# RADC-Power-S05-V00.net
KiCad netlist of a schematic drawn in Altium Designer
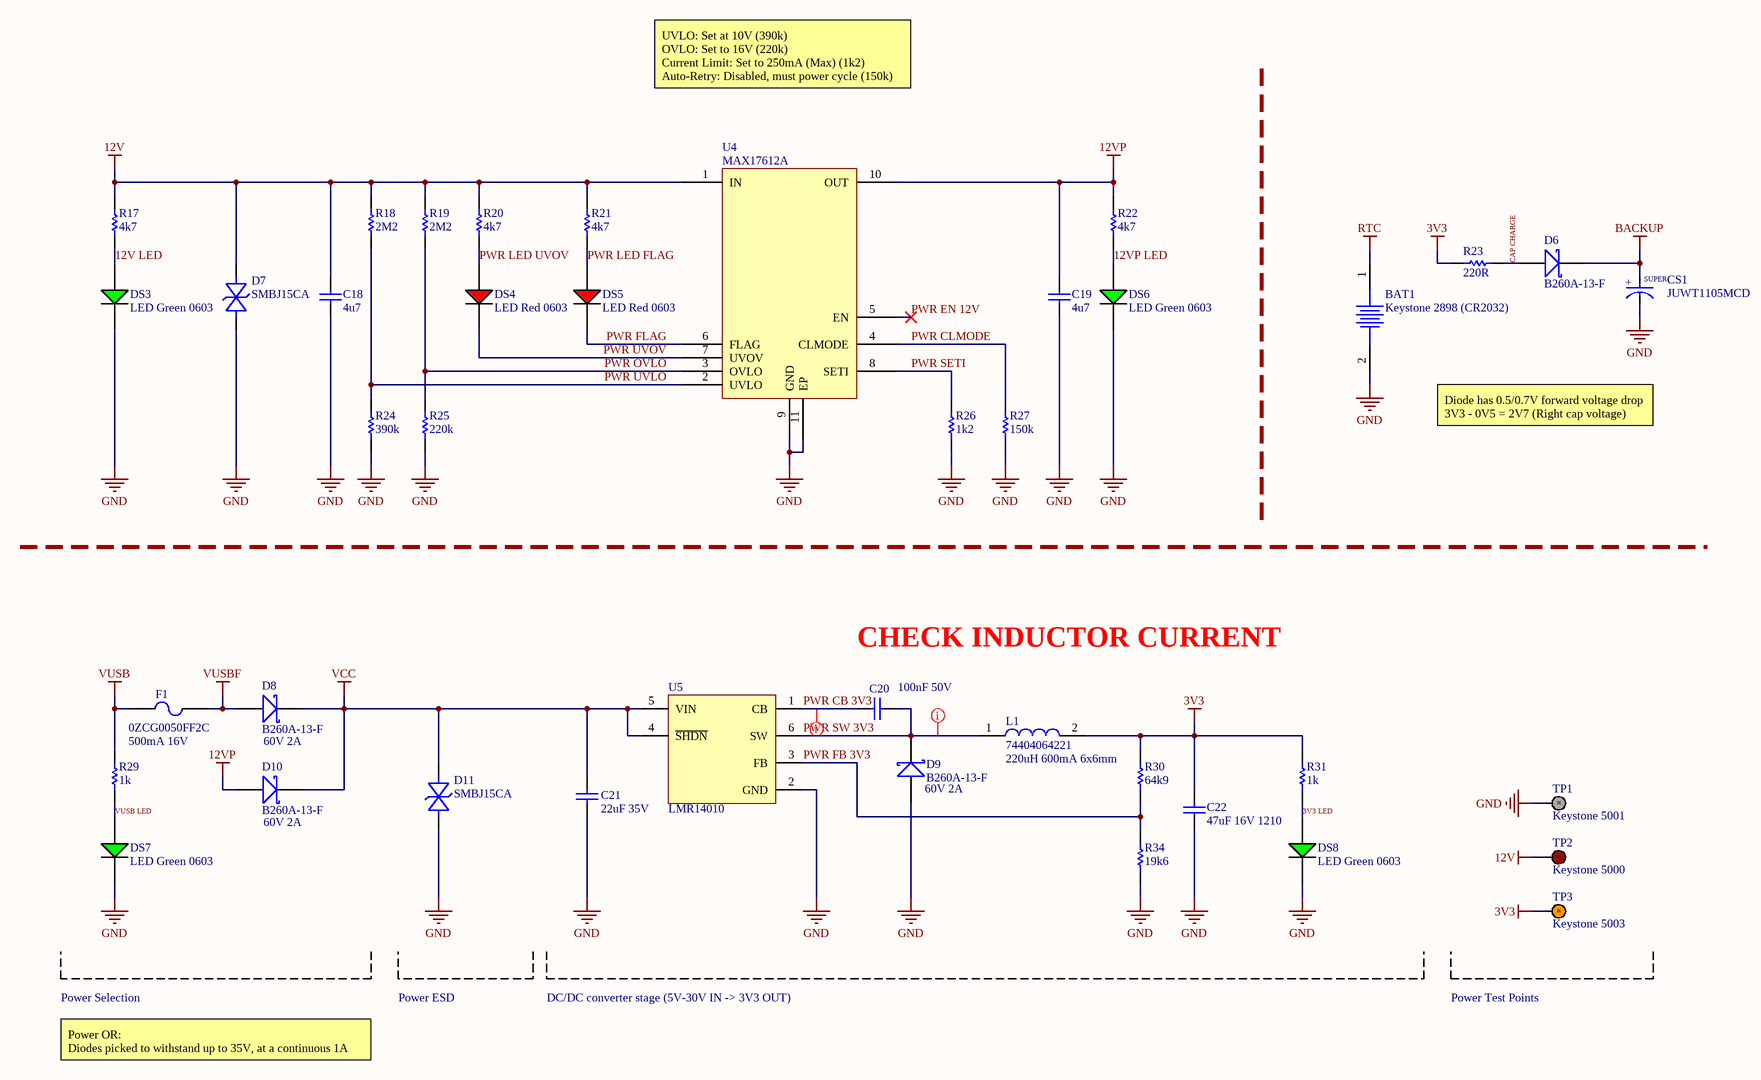
[diagram p0: RADC-Power-S05-V00.SchDoc]

(export (version "E")
  (design (tool "Eeschema 10.0.6"))
  (components
    (comp (ref "BAT1")
      (value "Keystone 2898 (CR2032)")
      (footprint "Keystone 2898")
      (description "Battery Retainer Coin, 20.0mm 1 Cell SMD (SMT) Tab")
      (libsource (lib "QUTMS_PowerSupplyLibrary") (part "Keystone 2898"))
    )
    (comp (ref "C18")
      (value "4u7")
      (footprint "Cap_Ceramic_0603")
      (description "Capacitor, Ceramic, SMD, 4u7, 50V, 5%, X7R, 0603")
      (libsource (lib "StandardCapacitors") (part "4u7 50V 5% X7R 0603"))
    )
    (comp (ref "C19")
      (value "4u7")
      (footprint "Cap_Ceramic_0603")
      (description "Capacitor, Ceramic, SMD, 4u7, 50V, 5%, X7R, 0603")
      (libsource (lib "StandardCapacitors") (part "4u7 50V 5% X7R 0603"))
    )
    (comp (ref "C20")
      (value "100nF 50V")
      (footprint "Cap_Ceramic_0603")
      (description "Capacitor, Ceramic, SMD, 100nF, 50V, 5%, X7R, 0603")
      (libsource (lib "StandardCapacitors") (part "100nF 50V 5% X7R 0603"))
    )
    (comp (ref "C21")
      (value "22uF 35V")
      (footprint "Cap_Ceramic_1206")
      (description "22µF ±20% 35V Ceramic Capacitor X5R 1206 (3216 Metric)")
      (libsource (lib "StandardCapacitors") (part "22uF 35V 20% X5R 1206"))
    )
    (comp (ref "C22")
      (value "47uF 16V 1210")
      (footprint "Cap_Ceramic_1210")
      (description "Capacitor, Ceramic, SMD, 47uF, 16V, 5%, X7R, 1210")
      (libsource (lib "StandardCapacitors") (part "47uF 16V 10% X7R 1210"))
    )
    (comp (ref "CS1")
      (value "JUWT1105MCD")
      (footprint "CAP_ALU_6.3mmD_9mmL")
      (description "1F (EDLC) Supercapacitor 2.7V Radial, Can 4Ohm @ 1kHz 1000 Hrs @ 70°C")
      (libsource (lib "StandardCapacitors") (part "JUWT1105MCD"))
    )
    (comp (ref "D6")
      (value "B260A-13-F")
      (footprint "SMA")
      (description "Diode, Schottky Barrier Rectifier, 60 V, 2 A, B260A-13-F")
      (libsource (lib "QUTMS_DiodeLibrary") (part "B260A-13-F"))
    )
    (comp (ref "D7")
      (value "SMBJ15CA")
      (footprint "SMB")
      (description "Diode, SMD, TVS Diode, 15V 24.4V, DO214AA/SMB")
      (libsource (lib "QUTMS_DiodeLibrary") (part "SMBJ15CA"))
    )
    (comp (ref "D8")
      (value "B260A-13-F")
      (footprint "SMA")
      (description "Diode, Schottky Barrier Rectifier, 60 V, 2 A, B260A-13-F")
      (libsource (lib "QUTMS_DiodeLibrary") (part "B260A-13-F"))
    )
    (comp (ref "D9")
      (value "B260A-13-F")
      (footprint "SMA")
      (description "Diode, Schottky Barrier Rectifier, 60 V, 2 A, B260A-13-F")
      (libsource (lib "QUTMS_DiodeLibrary") (part "B260A-13-F"))
    )
    (comp (ref "D10")
      (value "B260A-13-F")
      (footprint "SMA")
      (description "Diode, Schottky Barrier Rectifier, 60 V, 2 A, B260A-13-F")
      (libsource (lib "QUTMS_DiodeLibrary") (part "B260A-13-F"))
    )
    (comp (ref "D11")
      (value "SMBJ15CA")
      (footprint "SMB")
      (description "Diode, SMD, TVS Diode, 15V 24.4V, DO214AA/SMB")
      (libsource (lib "QUTMS_DiodeLibrary") (part "SMBJ15CA"))
    )
    (comp (ref "DS3")
      (value "LED Green 0603")
      (footprint "LED GREEN 0603")
      (libsource (lib "QUTMS_LEDLibrary") (part "LED Green 0603"))
    )
    (comp (ref "DS4")
      (value "LED Red 0603")
      (footprint "LED RED 0603")
      (libsource (lib "QUTMS_LEDLibrary") (part "LED Red 0603"))
    )
    (comp (ref "DS5")
      (value "LED Red 0603")
      (footprint "LED RED 0603")
      (libsource (lib "QUTMS_LEDLibrary") (part "LED Red 0603"))
    )
    (comp (ref "DS6")
      (value "LED Green 0603")
      (footprint "LED GREEN 0603")
      (libsource (lib "QUTMS_LEDLibrary") (part "LED Green 0603"))
    )
    (comp (ref "DS7")
      (value "LED Green 0603")
      (footprint "LED GREEN 0603")
      (libsource (lib "QUTMS_LEDLibrary") (part "LED Green 0603"))
    )
    (comp (ref "DS8")
      (value "LED Green 0603")
      (footprint "LED GREEN 0603")
      (libsource (lib "QUTMS_LEDLibrary") (part "LED Green 0603"))
    )
    (comp (ref "F1")
      (value "0ZCG0050FF2C")
      (footprint "1812 FUSE")
      (description "Polymeric PTC Resettable Fuse 16V 500mA Ih Surface Mount 1812 (4532 Metric), Concave")
      (libsource (lib "QUTMS_FuseLibrary") (part "0ZCG0050FF2C"))
    )
    (comp (ref "L1")
      (value "74404064221")
      (footprint "Inductor_6x6mm")
      (description "FIXED IND 220UH 660MA 850 MOHM")
      (libsource (lib "QUTMS_InductorLibrary") (part "74404064221"))
    )
    (comp (ref "R17")
      (value "4k7")
      (footprint "Res_ThinFilm_0603")
      (description "Resistor, SMD, 4k7, 0.1W, 5%, 0603")
      (libsource (lib "StandardResistors") (part "4k7 5% 0603"))
    )
    (comp (ref "R18")
      (value "2M2")
      (footprint "Res_ThinFilm_0603")
      (description "Resistor, SMD, 2M2, 0.1W, 5%, 0603")
      (libsource (lib "StandardResistors") (part "2M2 5% 0603"))
    )
    (comp (ref "R19")
      (value "2M2")
      (footprint "Res_ThinFilm_0603")
      (description "Resistor, SMD, 2M2, 0.1W, 5%, 0603")
      (libsource (lib "StandardResistors") (part "2M2 5% 0603"))
    )
    (comp (ref "R20")
      (value "4k7")
      (footprint "Res_ThinFilm_0603")
      (description "Resistor, SMD, 4k7, 0.1W, 5%, 0603")
      (libsource (lib "StandardResistors") (part "4k7 5% 0603"))
    )
    (comp (ref "R21")
      (value "4k7")
      (footprint "Res_ThinFilm_0603")
      (description "Resistor, SMD, 4k7, 0.1W, 5%, 0603")
      (libsource (lib "StandardResistors") (part "4k7 5% 0603"))
    )
    (comp (ref "R22")
      (value "4k7")
      (footprint "Res_ThinFilm_0603")
      (description "Resistor, SMD, 4k7, 0.1W, 5%, 0603")
      (libsource (lib "StandardResistors") (part "4k7 5% 0603"))
    )
    (comp (ref "R23")
      (value "220R")
      (footprint "Res_ThinFilm_0603")
      (description "Resistor, SMD, 220R, 0.1W, 5%, 0603")
      (libsource (lib "StandardResistors") (part "220R 5% 0603"))
    )
    (comp (ref "R24")
      (value "390k")
      (footprint "Res_ThinFilm_0603")
      (description "Resistor, SMD, 390k, 0.1W, 5%, 0603")
      (libsource (lib "StandardResistors") (part "390k 5% 0603"))
    )
    (comp (ref "R25")
      (value "220k")
      (footprint "Res_ThinFilm_0603")
      (description "Resistor, SMD, 220k, 0.1W, 5%, 0603")
      (libsource (lib "StandardResistors") (part "220k 5% 0603"))
    )
    (comp (ref "R26")
      (value "1k2")
      (footprint "Res_ThinFilm_0603")
      (description "Resistor, SMD, 1k2, 0.1W, 5%, 0603")
      (libsource (lib "StandardResistors") (part "1k2 5% 0603"))
    )
    (comp (ref "R27")
      (value "150k")
      (footprint "Res_ThinFilm_0603")
      (description "Resistor, SMD, 150k, 0.1W, 5%, 0603")
      (libsource (lib "StandardResistors") (part "150k 5%, 0603"))
    )
    (comp (ref "R29")
      (value "1k")
      (footprint "Res_ThinFilm_0603")
      (description "Resistor, SMD, 1k, 0.1W, 5%, 0603")
      (libsource (lib "StandardResistors") (part "1k 5% 0603"))
    )
    (comp (ref "R30")
      (value "64k9")
      (footprint "Res_ThinFilm_0603")
      (description "Resistor, SMD, 64k9, 0.1W, 5%, 0603")
      (libsource (lib "StandardResistors") (part "64k9 1% 0603"))
    )
    (comp (ref "R31")
      (value "1k")
      (footprint "Res_ThinFilm_0603")
      (description "Resistor, SMD, 1k, 0.1W, 5%, 0603")
      (libsource (lib "StandardResistors") (part "1k 5% 0603"))
    )
    (comp (ref "R34")
      (value "19k6")
      (footprint "Res_ThinFilm_0603")
      (description "Resistor, SMD, 19k6, 0.1W, 5%, 0603")
      (libsource (lib "StandardResistors") (part "19k6 1% 0603"))
    )
    (comp (ref "TP1")
      (value "Keystone 5001")
      (footprint "TestPointHoop_BLACK")
      (libsource (lib "StandardTest") (part "TestPoint_Hoop_Black"))
    )
    (comp (ref "TP2")
      (value "Keystone 5000")
      (footprint "TestPointHoop_RED")
      (libsource (lib "StandardTest") (part "TestPoint_Hoop_Red"))
    )
    (comp (ref "TP3")
      (value "Keystone 5003")
      (footprint "TestPointHoop_ORANGE")
      (libsource (lib "StandardTest") (part "TestPoint_Hoop_Orange"))
    )
    (comp (ref "U4")
      (value "MAX17612A")
      (footprint "10-Pin TDFN EP")
      (description "Overvoltage, Undervoltage Protection PMIC 10-TDFN-EP (3x3)")
      (libsource (lib "QUTMS_IntegratedCircuitLibrary") (part "MAX17612A"))
    )
    (comp (ref "U5")
      (value "LMR14010")
      (footprint "LMR14010")
      (libsource (lib "QUTMS_PowerSupplyLibrary") (part "LMR14010"))
    )
  )
  (nets
    (net (code "1") (name "/3V3 LED") (class "Default")
      (node (ref "DS8") (pin "1") (pinfunction "A_1") (pintype "passive"))
      (node (ref "R31") (pin "1") (pinfunction "1_1") (pintype "passive"))
    )
    (net (code "2") (name "/12V LED") (class "Default")
      (node (ref "DS3") (pin "1") (pinfunction "A_1") (pintype "passive"))
      (node (ref "R17") (pin "1") (pinfunction "1_1") (pintype "passive"))
    )
    (net (code "3") (name "/12VP LED") (class "Default")
      (node (ref "DS6") (pin "1") (pinfunction "A_1") (pintype "passive"))
      (node (ref "R22") (pin "1") (pinfunction "1_1") (pintype "passive"))
    )
    (net (code "4") (name "/CAP CHARGE") (class "Default")
      (node (ref "D6") (pin "A") (pinfunction "A_A") (pintype "passive"))
      (node (ref "R23") (pin "2") (pinfunction "2_2") (pintype "passive"))
    )
    (net (code "5") (name "/PWR CB 3V3") (class "Default")
      (node (ref "C20") (pin "1") (pinfunction "1_1") (pintype "passive"))
      (node (ref "U5") (pin "1") (pinfunction "CB_1") (pintype "passive"))
    )
    (net (code "6") (name "/PWR CLMODE") (class "Default")
      (node (ref "R27") (pin "2") (pinfunction "2_2") (pintype "passive"))
      (node (ref "U4") (pin "4") (pinfunction "CLMODE_4") (pintype "passive"))
    )
    (net (code "7") (name "/PWR EN 12V") (class "Default")
      (node (ref "U4") (pin "5") (pinfunction "EN_5") (pintype "passive+no_connect"))
    )
    (net (code "8") (name "/PWR FB 3V3") (class "Default")
      (node (ref "R30") (pin "1") (pinfunction "1_1") (pintype "passive"))
      (node (ref "R34") (pin "2") (pinfunction "2_2") (pintype "passive"))
      (node (ref "U5") (pin "3") (pinfunction "FB_3") (pintype "passive"))
    )
    (net (code "9") (name "/PWR FLAG") (class "Default")
      (node (ref "DS5") (pin "2") (pinfunction "C_2") (pintype "passive"))
      (node (ref "U4") (pin "6") (pinfunction "FLAG_6") (pintype "passive"))
    )
    (net (code "10") (name "/PWR LED FLAG") (class "Default")
      (node (ref "DS5") (pin "1") (pinfunction "A_1") (pintype "passive"))
      (node (ref "R21") (pin "1") (pinfunction "1_1") (pintype "passive"))
    )
    (net (code "11") (name "/PWR LED UVOV") (class "Default")
      (node (ref "DS4") (pin "1") (pinfunction "A_1") (pintype "passive"))
      (node (ref "R20") (pin "1") (pinfunction "1_1") (pintype "passive"))
    )
    (net (code "12") (name "/PWR OVLO") (class "Default")
      (node (ref "R19") (pin "1") (pinfunction "1_1") (pintype "passive"))
      (node (ref "R25") (pin "2") (pinfunction "2_2") (pintype "passive"))
      (node (ref "U4") (pin "3") (pinfunction "OVLO_3") (pintype "passive"))
    )
    (net (code "13") (name "/PWR SETI") (class "Default")
      (node (ref "R26") (pin "2") (pinfunction "2_2") (pintype "passive"))
      (node (ref "U4") (pin "8") (pinfunction "SETI_8") (pintype "passive"))
    )
    (net (code "14") (name "/PWR SW 3V3") (class "Default")
      (node (ref "C20") (pin "2") (pinfunction "2_2") (pintype "passive"))
      (node (ref "D9") (pin "K") (pinfunction "K_K") (pintype "passive"))
      (node (ref "L1") (pin "1") (pinfunction "1_1") (pintype "passive"))
      (node (ref "U5") (pin "6") (pinfunction "SW_6") (pintype "passive"))
    )
    (net (code "15") (name "/PWR UVLO") (class "Default")
      (node (ref "R18") (pin "1") (pinfunction "1_1") (pintype "passive"))
      (node (ref "R24") (pin "2") (pinfunction "2_2") (pintype "passive"))
      (node (ref "U4") (pin "2") (pinfunction "UVLO_2") (pintype "passive"))
    )
    (net (code "16") (name "/PWR UVOV") (class "Default")
      (node (ref "DS4") (pin "2") (pinfunction "C_2") (pintype "passive"))
      (node (ref "U4") (pin "7") (pinfunction "UVOV_7") (pintype "passive"))
    )
    (net (code "17") (name "/VUSB LED") (class "Default")
      (node (ref "DS7") (pin "1") (pinfunction "A_1") (pintype "passive"))
      (node (ref "R29") (pin "1") (pinfunction "1_1") (pintype "passive"))
    )
    (net (code "18") (name "3V3") (class "Default")
      (node (ref "C22") (pin "2") (pinfunction "2_2") (pintype "passive"))
      (node (ref "L1") (pin "2") (pinfunction "2_2") (pintype "passive"))
      (node (ref "R23") (pin "1") (pinfunction "1_1") (pintype "passive"))
      (node (ref "R30") (pin "2") (pinfunction "2_2") (pintype "passive"))
      (node (ref "R31") (pin "2") (pinfunction "2_2") (pintype "passive"))
      (node (ref "TP3") (pin "1") (pinfunction "1_1") (pintype "passive"))
    )
    (net (code "19") (name "12V") (class "Default")
      (node (ref "C18") (pin "2") (pinfunction "2_2") (pintype "passive"))
      (node (ref "D7") (pin "A") (pinfunction "Anode_A") (pintype "passive"))
      (node (ref "R17") (pin "2") (pinfunction "2_2") (pintype "passive"))
      (node (ref "R18") (pin "2") (pinfunction "2_2") (pintype "passive"))
      (node (ref "R19") (pin "2") (pinfunction "2_2") (pintype "passive"))
      (node (ref "R20") (pin "2") (pinfunction "2_2") (pintype "passive"))
      (node (ref "R21") (pin "2") (pinfunction "2_2") (pintype "passive"))
      (node (ref "TP2") (pin "1") (pinfunction "1_1") (pintype "passive"))
      (node (ref "U4") (pin "1") (pinfunction "IN_1") (pintype "passive"))
    )
    (net (code "20") (name "12VP") (class "Default")
      (node (ref "C19") (pin "2") (pinfunction "2_2") (pintype "passive"))
      (node (ref "D10") (pin "A") (pinfunction "A_A") (pintype "passive"))
      (node (ref "R22") (pin "2") (pinfunction "2_2") (pintype "passive"))
      (node (ref "U4") (pin "10") (pinfunction "OUT_10") (pintype "passive"))
    )
    (net (code "21") (name "BACKUP") (class "Default")
      (node (ref "CS1") (pin "A") (pinfunction "A_A") (pintype "passive"))
      (node (ref "D6") (pin "K") (pinfunction "K_K") (pintype "passive"))
    )
    (net (code "22") (name "GND") (class "Default")
      (node (ref "BAT1") (pin "2") (pinfunction "1_2") (pintype "passive"))
      (node (ref "C18") (pin "1") (pinfunction "1_1") (pintype "passive"))
      (node (ref "C19") (pin "1") (pinfunction "1_1") (pintype "passive"))
      (node (ref "C21") (pin "1") (pinfunction "1_1") (pintype "passive"))
      (node (ref "C22") (pin "1") (pinfunction "1_1") (pintype "passive"))
      (node (ref "CS1") (pin "K") (pinfunction "K_K") (pintype "passive"))
      (node (ref "D11") (pin "K") (pinfunction "Cathode_K") (pintype "passive"))
      (node (ref "D7") (pin "K") (pinfunction "Cathode_K") (pintype "passive"))
      (node (ref "D9") (pin "A") (pinfunction "A_A") (pintype "passive"))
      (node (ref "DS3") (pin "2") (pinfunction "C_2") (pintype "passive"))
      (node (ref "DS6") (pin "2") (pinfunction "C_2") (pintype "passive"))
      (node (ref "DS7") (pin "2") (pinfunction "C_2") (pintype "passive"))
      (node (ref "DS8") (pin "2") (pinfunction "C_2") (pintype "passive"))
      (node (ref "R24") (pin "1") (pinfunction "1_1") (pintype "passive"))
      (node (ref "R25") (pin "1") (pinfunction "1_1") (pintype "passive"))
      (node (ref "R26") (pin "1") (pinfunction "1_1") (pintype "passive"))
      (node (ref "R27") (pin "1") (pinfunction "1_1") (pintype "passive"))
      (node (ref "R34") (pin "1") (pinfunction "1_1") (pintype "passive"))
      (node (ref "TP1") (pin "1") (pinfunction "1_1") (pintype "passive"))
      (node (ref "U4") (pin "11") (pinfunction "EP_11") (pintype "passive"))
      (node (ref "U4") (pin "9") (pinfunction "GND_9") (pintype "passive"))
      (node (ref "U5") (pin "2") (pinfunction "GND_2") (pintype "passive"))
    )
    (net (code "23") (name "RTC") (class "Default")
      (node (ref "BAT1") (pin "1") (pinfunction "0_1") (pintype "passive"))
    )
    (net (code "24") (name "VCC") (class "Default")
      (node (ref "C21") (pin "2") (pinfunction "2_2") (pintype "passive"))
      (node (ref "D10") (pin "K") (pinfunction "K_K") (pintype "passive"))
      (node (ref "D11") (pin "A") (pinfunction "Anode_A") (pintype "passive"))
      (node (ref "D8") (pin "K") (pinfunction "K_K") (pintype "passive"))
      (node (ref "U5") (pin "4") (pinfunction "~{SHDN}_4") (pintype "passive"))
      (node (ref "U5") (pin "5") (pinfunction "VIN_5") (pintype "passive"))
    )
    (net (code "25") (name "VUSB") (class "Default")
      (node (ref "F1") (pin "1") (pinfunction "1_1") (pintype "passive"))
      (node (ref "R29") (pin "2") (pinfunction "2_2") (pintype "passive"))
    )
    (net (code "26") (name "VUSBF") (class "Default")
      (node (ref "D8") (pin "A") (pinfunction "A_A") (pintype "passive"))
      (node (ref "F1") (pin "2") (pinfunction "2_2") (pintype "passive"))
    )
  )
)
